# bluetooth.net
KiCad netlist of a schematic drawn in Altium Designer
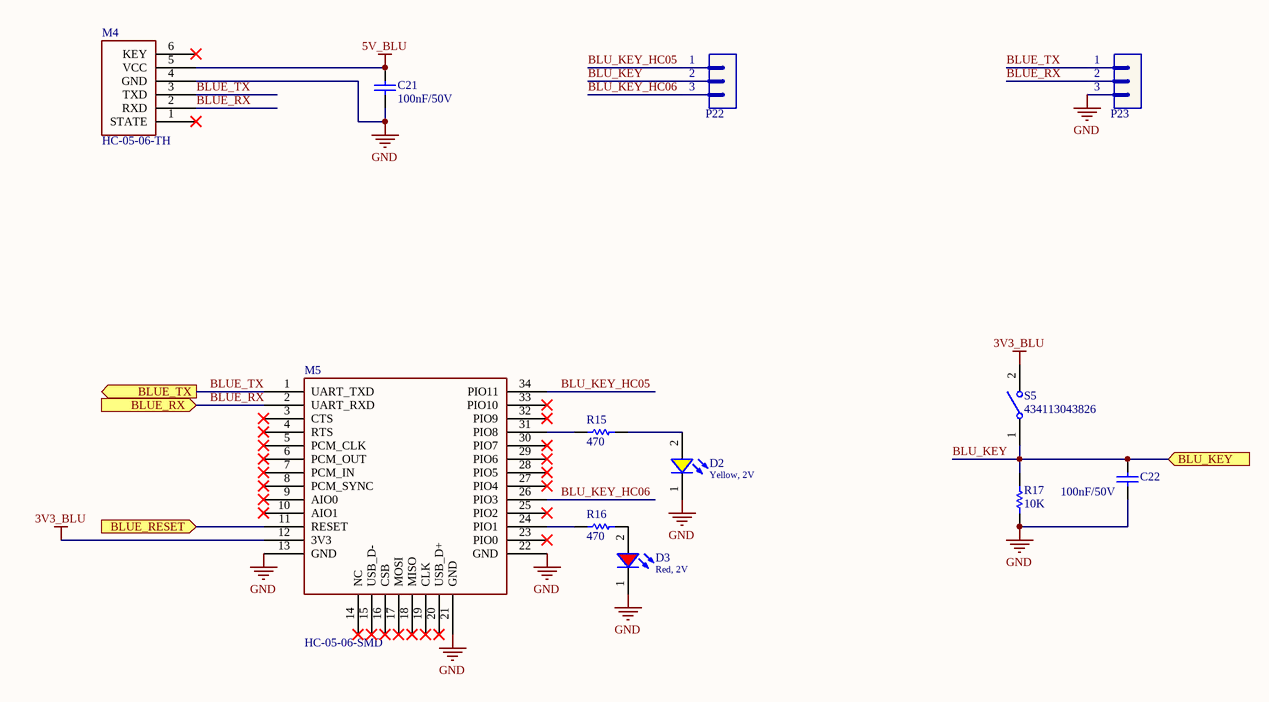
[diagram p0: bluetooth.SchDoc]

(export (version "E")
  (design (tool "Eeschema 10.0.6"))
  (components
    (comp (ref "C21")
      (value "100nF/50V")
      (footprint "CAP-SM-0805")
      (description "CAP CER 0.1UF 50V Y5V 0805")
      (fields
        (field (name "MANUFACTURER") "Samsung Electro-Mechanics")
        (field (name "MANUFACTURER PART NUMBER") "CL21F104ZBCNNNC")
      )
      (libsource (lib "Capacitor") (part "Cap-100nF-50V-0805"))
    )
    (comp (ref "C22")
      (value "100nF/50V")
      (footprint "CAP-SM-0805")
      (description "CAP CER 0.1UF 50V Y5V 0805")
      (fields
        (field (name "MANUFACTURER") "Samsung Electro-Mechanics")
        (field (name "MANUFACTURER PART NUMBER") "CL21F104ZBCNNNC")
      )
      (libsource (lib "Capacitor") (part "Cap-100nF-50V-0805"))
    )
    (comp (ref "D2")
      (value "Yellow, 2V")
      (footprint "WL-SMCW_0805")
      (description "WL-SMCW SMT Mono-color Chip LED Waterclear, size 0805, Yellow, 2V, 140deg")
      (fields
        (field (name "PART NUMBER") "150080YS75000")
        (field (name "LOCAL SUPPLIER PART NUMBER") "x")
        (field (name "PUBLISHER") "Wurth Elektronik")
      )
      (libsource (lib "LED") (part "0805-Yellow"))
    )
    (comp (ref "D3")
      (value "Red, 2V")
      (footprint "WL-SMCW_0805")
      (description "WL-SMCW SMT Mono-color Chip LED Waterclear, size 0805, Red, 2V, 140deg")
      (fields
        (field (name "PART NUMBER") "150080RS75000")
        (field (name "LOCAL SUPPLIER PARTNUMBER") "x")
        (field (name "PUBLISHER") "Wurth Elektronik")
      )
      (libsource (lib "LED") (part "0805-Red"))
    )
    (comp (ref "M4")
      (value "HC-05-06-TH")
      (footprint "HC-05-06-TH")
      (libsource (lib "PIFWRobot") (part "HC-05-06-TH"))
    )
    (comp (ref "M5")
      (value "HC-05-06-SMD")
      (footprint "HC-05-06-SMD")
      (libsource (lib "PIFWRobot") (part "HC-05-06-SMD"))
    )
    (comp (ref "P22")
      (value "Header 3")
      (footprint "JP3")
      (description "Header, 3-Pin")
      (fields (field (name "LOCAL SUPPLIER PART NUMBER") "x") (field (name "PUBLISHER") "Altium Limited"))
      (libsource (lib "Header-Connector") (part "Header 3"))
    )
    (comp (ref "P23")
      (value "Header 3")
      (footprint "JP3")
      (description "Header, 3-Pin")
      (fields (field (name "LOCAL SUPPLIER PART NUMBER") "x") (field (name "PUBLISHER") "Altium Limited"))
      (libsource (lib "Header-Connector") (part "Header 3"))
    )
    (comp (ref "R15")
      (value "470")
      (footprint "Resistor:RES-SM-0805")
      (description "RES 470 OHM JUMPER 0805")
      (fields
        (field (name "MANUFACTURER") "YAG6006CT-ND")
        (field (name "MANUFACTURER PART NUMBER") "PE0805FRF7W0R047L")
      )
      (libsource (lib "Resistor") (part "Res-470-0805"))
    )
    (comp (ref "R16")
      (value "470")
      (footprint "Resistor:RES-SM-0805")
      (description "RES 470 OHM JUMPER 0805")
      (fields
        (field (name "MANUFACTURER") "YAG6006CT-ND")
        (field (name "MANUFACTURER PART NUMBER") "PE0805FRF7W0R047L")
      )
      (libsource (lib "Resistor") (part "Res-470-0805"))
    )
    (comp (ref "R17")
      (value "10K")
      (footprint "Resistor:RES-SM-0805")
      (description "RES 10K OHM 1% 1/4W 0805")
      (fields
        (field (name "MANUFACTURER") "Stackpole Electronics Inc")
        (field (name "MANUFACTURER PART NUMBER") "RNCP0805FTD10K0")
      )
      (libsource (lib "Resistor") (part "Res-10k-0805"))
    )
    (comp (ref "S5")
      (value "434113043826")
      (footprint "434113043826")
      (description "WS-TASV J-Bend SMT Tact Switch 6x3.5mm, height 4.3mm, 260gf")
      (fields (field (name "LOCAL SUPPLIER PART NUMBER") "x") (field (name "PUBLISHER") "Wurth Elektronik"))
      (libsource (lib "switch") (part "434113043826"))
    )
  )
  (nets
    (net (code "1") (name "/BLUE_RESET") (class "Default")
      (node (ref "M5") (pin "11") (pinfunction "RESET_11") (pintype "passive"))
    )
    (net (code "2") (name "/BLUE_RX") (class "Default")
      (node (ref "M4") (pin "2") (pinfunction "RXD_2") (pintype "passive"))
      (node (ref "M5") (pin "2") (pinfunction "UART_RXD_2") (pintype "passive"))
      (node (ref "P23") (pin "2") (pinfunction "2_2") (pintype "passive"))
    )
    (net (code "3") (name "/BLUE_TX") (class "Default")
      (node (ref "M4") (pin "3") (pinfunction "TXD_3") (pintype "passive"))
      (node (ref "M5") (pin "1") (pinfunction "UART_TXD_1") (pintype "passive"))
      (node (ref "P23") (pin "1") (pinfunction "1_1") (pintype "passive"))
    )
    (net (code "4") (name "/BLU_KEY") (class "Default")
      (node (ref "C22") (pin "2") (pinfunction "2_2") (pintype "passive"))
      (node (ref "P22") (pin "2") (pinfunction "2_2") (pintype "passive"))
      (node (ref "R17") (pin "1") (pinfunction "1_1") (pintype "passive"))
      (node (ref "S5") (pin "1") (pinfunction "1_1") (pintype "passive"))
    )
    (net (code "5") (name "/BLU_KEY_HC05") (class "Default")
      (node (ref "M5") (pin "34") (pinfunction "PIO11_34") (pintype "passive"))
      (node (ref "P22") (pin "1") (pinfunction "1_1") (pintype "passive"))
    )
    (net (code "6") (name "/BLU_KEY_HC06") (class "Default")
      (node (ref "M5") (pin "26") (pinfunction "PIO3_26") (pintype "passive"))
      (node (ref "P22") (pin "3") (pinfunction "3_3") (pintype "passive"))
    )
    (net (code "7") (name "3V3_BLU") (class "Default")
      (node (ref "M5") (pin "12") (pinfunction "3V3_12") (pintype "passive"))
      (node (ref "S5") (pin "2") (pinfunction "2_2") (pintype "passive"))
    )
    (net (code "8") (name "5V_BLU") (class "Default")
      (node (ref "C21") (pin "2") (pinfunction "2_2") (pintype "passive"))
      (node (ref "M4") (pin "5") (pinfunction "VCC_5") (pintype "passive"))
    )
    (net (code "9") (name "GND") (class "Default")
      (node (ref "C21") (pin "1") (pinfunction "1_1") (pintype "passive"))
      (node (ref "C22") (pin "1") (pinfunction "1_1") (pintype "passive"))
      (node (ref "D2") (pin "1") (pinfunction "K_1") (pintype "passive"))
      (node (ref "D3") (pin "1") (pinfunction "K_1") (pintype "passive"))
      (node (ref "M4") (pin "4") (pinfunction "GND_4") (pintype "passive"))
      (node (ref "M5") (pin "13") (pinfunction "GND_13") (pintype "passive"))
      (node (ref "M5") (pin "21") (pinfunction "GND_21") (pintype "passive"))
      (node (ref "M5") (pin "22") (pinfunction "GND_22") (pintype "passive"))
      (node (ref "P23") (pin "3") (pinfunction "3_3") (pintype "passive"))
      (node (ref "R17") (pin "2") (pinfunction "2_2") (pintype "passive"))
    )
    (net (code "10") (name "Net-(D2-A)") (class "Default")
      (node (ref "D2") (pin "2") (pinfunction "A_2") (pintype "passive"))
      (node (ref "R15") (pin "2") (pinfunction "2_2") (pintype "passive"))
    )
    (net (code "11") (name "Net-(D3-A)") (class "Default")
      (node (ref "D3") (pin "2") (pinfunction "A_2") (pintype "passive"))
      (node (ref "R16") (pin "2") (pinfunction "2_2") (pintype "passive"))
    )
    (net (code "12") (name "Net-(M5-PIO1)") (class "Default")
      (node (ref "M5") (pin "24") (pinfunction "PIO1_24") (pintype "passive"))
      (node (ref "R16") (pin "1") (pinfunction "1_1") (pintype "passive"))
    )
    (net (code "13") (name "Net-(M5-PIO8)") (class "Default")
      (node (ref "M5") (pin "31") (pinfunction "PIO8_31") (pintype "passive"))
      (node (ref "R15") (pin "1") (pinfunction "1_1") (pintype "passive"))
    )
    (net (code "14") (name "unconnected-(M4-KEY-Pad6)") (class "Default")
      (node (ref "M4") (pin "6") (pinfunction "KEY_6") (pintype "passive+no_connect"))
    )
    (net (code "15") (name "unconnected-(M4-STATE-Pad1)") (class "Default")
      (node (ref "M4") (pin "1") (pinfunction "STATE_1") (pintype "passive+no_connect"))
    )
    (net (code "16") (name "unconnected-(M5-AIO0-Pad9)") (class "Default")
      (node (ref "M5") (pin "9") (pinfunction "AIO0_9") (pintype "passive+no_connect"))
    )
    (net (code "17") (name "unconnected-(M5-AIO1-Pad10)") (class "Default")
      (node (ref "M5") (pin "10") (pinfunction "AIO1_10") (pintype "passive+no_connect"))
    )
    (net (code "18") (name "unconnected-(M5-CLK-Pad19)") (class "Default")
      (node (ref "M5") (pin "19") (pinfunction "CLK_19") (pintype "passive+no_connect"))
    )
    (net (code "19") (name "unconnected-(M5-CSB-Pad16)") (class "Default")
      (node (ref "M5") (pin "16") (pinfunction "CSB_16") (pintype "passive+no_connect"))
    )
    (net (code "20") (name "unconnected-(M5-CTS-Pad3)") (class "Default")
      (node (ref "M5") (pin "3") (pinfunction "CTS_3") (pintype "passive+no_connect"))
    )
    (net (code "21") (name "unconnected-(M5-MISO-Pad18)") (class "Default")
      (node (ref "M5") (pin "18") (pinfunction "MISO_18") (pintype "passive+no_connect"))
    )
    (net (code "22") (name "unconnected-(M5-MOSI-Pad17)") (class "Default")
      (node (ref "M5") (pin "17") (pinfunction "MOSI_17") (pintype "passive+no_connect"))
    )
    (net (code "23") (name "unconnected-(M5-NC-Pad14)") (class "Default")
      (node (ref "M5") (pin "14") (pinfunction "NC_14") (pintype "passive+no_connect"))
    )
    (net (code "24") (name "unconnected-(M5-PCM_CLK-Pad5)") (class "Default")
      (node (ref "M5") (pin "5") (pinfunction "PCM_CLK_5") (pintype "passive+no_connect"))
    )
    (net (code "25") (name "unconnected-(M5-PCM_IN-Pad7)") (class "Default")
      (node (ref "M5") (pin "7") (pinfunction "PCM_IN_7") (pintype "passive+no_connect"))
    )
    (net (code "26") (name "unconnected-(M5-PCM_OUT-Pad6)") (class "Default")
      (node (ref "M5") (pin "6") (pinfunction "PCM_OUT_6") (pintype "passive+no_connect"))
    )
    (net (code "27") (name "unconnected-(M5-PCM_SYNC-Pad8)") (class "Default")
      (node (ref "M5") (pin "8") (pinfunction "PCM_SYNC_8") (pintype "passive+no_connect"))
    )
    (net (code "28") (name "unconnected-(M5-PIO0-Pad23)") (class "Default")
      (node (ref "M5") (pin "23") (pinfunction "PIO0_23") (pintype "passive+no_connect"))
    )
    (net (code "29") (name "unconnected-(M5-PIO2-Pad25)") (class "Default")
      (node (ref "M5") (pin "25") (pinfunction "PIO2_25") (pintype "passive+no_connect"))
    )
    (net (code "30") (name "unconnected-(M5-PIO4-Pad27)") (class "Default")
      (node (ref "M5") (pin "27") (pinfunction "PIO4_27") (pintype "passive+no_connect"))
    )
    (net (code "31") (name "unconnected-(M5-PIO5-Pad28)") (class "Default")
      (node (ref "M5") (pin "28") (pinfunction "PIO5_28") (pintype "passive+no_connect"))
    )
    (net (code "32") (name "unconnected-(M5-PIO6-Pad29)") (class "Default")
      (node (ref "M5") (pin "29") (pinfunction "PIO6_29") (pintype "passive+no_connect"))
    )
    (net (code "33") (name "unconnected-(M5-PIO7-Pad30)") (class "Default")
      (node (ref "M5") (pin "30") (pinfunction "PIO7_30") (pintype "passive+no_connect"))
    )
    (net (code "34") (name "unconnected-(M5-PIO9-Pad32)") (class "Default")
      (node (ref "M5") (pin "32") (pinfunction "PIO9_32") (pintype "passive+no_connect"))
    )
    (net (code "35") (name "unconnected-(M5-PIO10-Pad33)") (class "Default")
      (node (ref "M5") (pin "33") (pinfunction "PIO10_33") (pintype "passive+no_connect"))
    )
    (net (code "36") (name "unconnected-(M5-RTS-Pad4)") (class "Default")
      (node (ref "M5") (pin "4") (pinfunction "RTS_4") (pintype "passive+no_connect"))
    )
    (net (code "37") (name "unconnected-(M5-USB_D+-Pad20)") (class "Default")
      (node (ref "M5") (pin "20") (pinfunction "USB_D+_20") (pintype "passive+no_connect"))
    )
    (net (code "38") (name "unconnected-(M5-USB_D--Pad15)") (class "Default")
      (node (ref "M5") (pin "15") (pinfunction "USB_D-_15") (pintype "passive+no_connect"))
    )
  )
)
